# charger.net
KiCad netlist of a schematic drawn in EAGLE
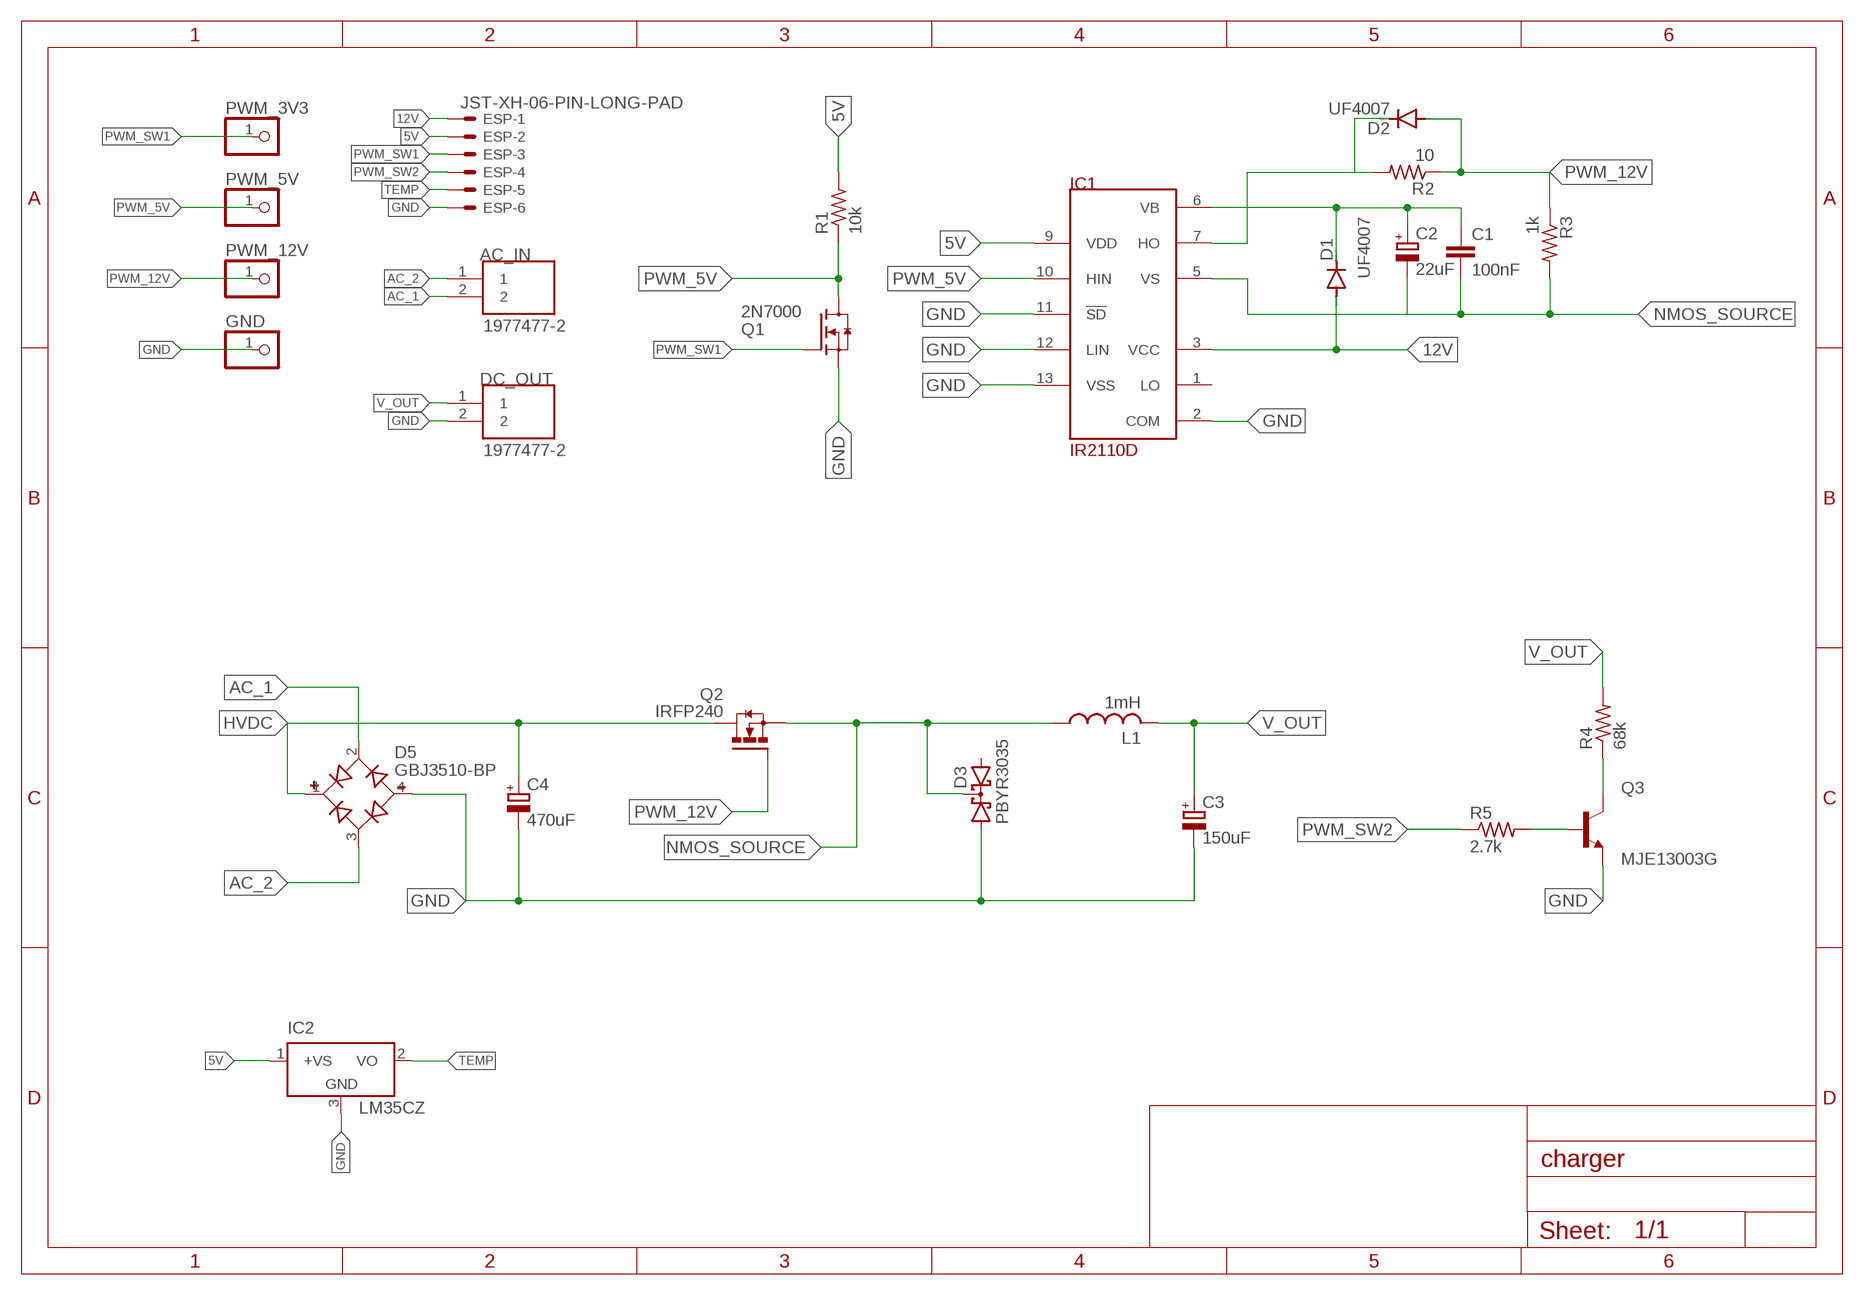
[diagram p0: schematic, sheet 1]

(export (version "E")
  (design (tool "Eeschema 10.0.6"))
  (components
    (comp (ref "AC_IN")
      (value "1977477-2")
      (footprint "eagle-import:TE_1977477-2")
      (fields (field (name "MF") "TE Connectivity"))
      (libsource (lib "eagle-import") (part "1977477-2"))
    )
    (comp (ref "C1")
      (value "100nF")
      (footprint "eagle-import:C025-025X050")
      (libsource (lib "eagle-import") (part "C-EU025-025X050"))
    )
    (comp (ref "C2")
      (value "22uF")
      (footprint "eagle-import:E2,5-6E")
      (libsource (lib "eagle-import") (part "CPOL-EUE2,5-6E"))
    )
    (comp (ref "C3")
      (value "150uF")
      (footprint "eagle-import:E7,5-18")
      (libsource (lib "eagle-import") (part "CPOL-EUE7.5-18"))
    )
    (comp (ref "C4")
      (value "470uF")
      (footprint "eagle-import:EB35D")
      (libsource (lib "eagle-import") (part "CPOL-EUE10-35"))
    )
    (comp (ref "D1")
      (value "UF4007")
      (footprint "eagle-import:DO34-7")
      (libsource (lib "eagle-import") (part "BAS15"))
    )
    (comp (ref "D2")
      (value "UF4007")
      (footprint "eagle-import:DO34-7")
      (libsource (lib "eagle-import") (part "BAS15"))
    )
    (comp (ref "D3")
      (value "PBYR3035")
      (footprint "eagle-import:SOT93S")
      (libsource (lib "eagle-import") (part "PBYR3035"))
    )
    (comp (ref "D5")
      (value "GBJ3510-BP")
      (footprint "eagle-import:DIOB_GBJ3510-BP")
      (fields (field (name "MF") "Micro Commercial"))
      (libsource (lib "eagle-import") (part "GBJ3510-BP"))
    )
    (comp (ref "DC_OUT")
      (value "1977477-2")
      (footprint "eagle-import:TE_1977477-2")
      (fields (field (name "MF") "TE Connectivity"))
      (libsource (lib "eagle-import") (part "1977477-2"))
    )
    (comp (ref "ESP")
      (value "JST-XH-06-PIN-LONG-PAD")
      (footprint "eagle-import:JST-XH-06-PACKAGE-LONG-PAD")
      (libsource (lib "eagle-import") (part "JST-XH-06-PIN-LONG-PAD"))
    )
    (comp (ref "GND")
      (value "PINHD-1X1")
      (footprint "eagle-import:1X01")
      (libsource (lib "eagle-import") (part "PINHD-1X1"))
    )
    (comp (ref "IC1")
      (value "IR2110D")
      (footprint "eagle-import:DIL14")
      (libsource (lib "eagle-import") (part "IR2110D"))
    )
    (comp (ref "IC2")
      (value "LM35CZ")
      (footprint "eagle-import:TO92")
      (libsource (lib "eagle-import") (part "LM35CZ"))
    )
    (comp (ref "L1")
      (value "1mH")
      (footprint "eagle-import:TJ7-U1")
      (libsource (lib "eagle-import") (part "L-USTJ7-U1"))
    )
    (comp (ref "PWM_3V3")
      (value "PINHD-1X1")
      (footprint "eagle-import:1X01")
      (libsource (lib "eagle-import") (part "PINHD-1X1"))
    )
    (comp (ref "PWM_5V")
      (value "PINHD-1X1")
      (footprint "eagle-import:1X01")
      (libsource (lib "eagle-import") (part "PINHD-1X1"))
    )
    (comp (ref "PWM_12V")
      (value "PINHD-1X1")
      (footprint "eagle-import:1X01")
      (libsource (lib "eagle-import") (part "PINHD-1X1"))
    )
    (comp (ref "Q1")
      (value "2N7000")
      (footprint "eagle-import:TO92")
      (fields (field (name "MF") "STMicroelectronics"))
      (libsource (lib "eagle-import") (part "2N7000"))
    )
    (comp (ref "Q2")
      (value "IRFP240")
      (footprint "eagle-import:TO247AC")
      (fields (field (name "MF") "Vishay Siliconix"))
      (libsource (lib "eagle-import") (part "IRFP240"))
    )
    (comp (ref "Q3")
      (value "MJE13003G")
      (footprint "eagle-import:TO229P780X300X1364-3")
      (fields (field (name "MF") "ON Semiconductor"))
      (libsource (lib "eagle-import") (part "MJE13003G"))
    )
    (comp (ref "R1")
      (value "10k")
      (footprint "eagle-import:0204_7")
      (libsource (lib "eagle-import") (part "R-US_0204/7"))
    )
    (comp (ref "R2")
      (value "10")
      (footprint "eagle-import:0204_7")
      (libsource (lib "eagle-import") (part "R-US_0204/7"))
    )
    (comp (ref "R3")
      (value "1k")
      (footprint "eagle-import:0204_7")
      (libsource (lib "eagle-import") (part "R-US_0204/7"))
    )
    (comp (ref "R4")
      (value "68k")
      (footprint "eagle-import:0204_7")
      (libsource (lib "eagle-import") (part "R-US_0204/7"))
    )
    (comp (ref "R5")
      (value "2.7k")
      (footprint "eagle-import:0204_7")
      (libsource (lib "eagle-import") (part "R-US_0204/7"))
    )
  )
  (nets
    (net (code "1") (name "5V") (class "Default")
      (node (ref "ESP") (pin "2") (pinfunction "S_2") (pintype "passive"))
      (node (ref "IC1") (pin "9") (pinfunction "VDD_9") (pintype "power_in"))
      (node (ref "IC2") (pin "1") (pinfunction "+VS_1") (pintype "input"))
      (node (ref "R1") (pin "2") (pinfunction "2_2") (pintype "passive"))
    )
    (net (code "2") (name "12V") (class "Default")
      (node (ref "D1") (pin "A") (pinfunction "A_A") (pintype "passive"))
      (node (ref "ESP") (pin "1") (pinfunction "S_1") (pintype "passive"))
      (node (ref "IC1") (pin "3") (pinfunction "VCC_3") (pintype "power_in"))
    )
    (net (code "3") (name "AC_1") (class "Default")
      (node (ref "AC_IN") (pin "2") (pinfunction "2_2") (pintype "passive"))
      (node (ref "D5") (pin "2") (pinfunction "AC1_2") (pintype "passive"))
    )
    (net (code "4") (name "AC_2") (class "Default")
      (node (ref "AC_IN") (pin "1") (pinfunction "1_1") (pintype "passive"))
      (node (ref "D5") (pin "3") (pinfunction "AC2_3") (pintype "passive"))
    )
    (net (code "5") (name "GND") (class "Default")
      (node (ref "C3") (pin "-") (pinfunction "-_-") (pintype "passive"))
      (node (ref "C4") (pin "-") (pinfunction "-_-") (pintype "passive"))
      (node (ref "D3") (pin "A1") (pinfunction "A1_A1") (pintype "passive"))
      (node (ref "D5") (pin "4") (pinfunction "-_4") (pintype "passive"))
      (node (ref "DC_OUT") (pin "2") (pinfunction "2_2") (pintype "passive"))
      (node (ref "ESP") (pin "6") (pinfunction "S_6") (pintype "passive"))
      (node (ref "GND") (pin "1") (pinfunction "1_1") (pintype "passive"))
      (node (ref "IC1") (pin "11") (pinfunction "~{SD}_11") (pintype "input"))
      (node (ref "IC1") (pin "12") (pinfunction "LIN_12") (pintype "input"))
      (node (ref "IC1") (pin "13") (pinfunction "VSS_13") (pintype "power_in"))
      (node (ref "IC1") (pin "2") (pinfunction "COM_2") (pintype "power_in"))
      (node (ref "IC2") (pin "3") (pinfunction "GND_3") (pintype "power_in"))
      (node (ref "Q1") (pin "1") (pinfunction "S_1") (pintype "passive"))
      (node (ref "Q3") (pin "3") (pinfunction "E_3") (pintype "passive"))
    )
    (net (code "6") (name "HVDC") (class "Default")
      (node (ref "C4") (pin "+") (pinfunction "+_+") (pintype "passive"))
      (node (ref "D5") (pin "1") (pinfunction "+_1") (pintype "passive"))
      (node (ref "Q2") (pin "2") (pinfunction "D_2") (pintype "passive"))
    )
    (net (code "7") (name "NMOS_SOURCE") (class "Default")
      (node (ref "C1") (pin "2") (pinfunction "2_2") (pintype "passive"))
      (node (ref "C2") (pin "-") (pinfunction "-_-") (pintype "passive"))
      (node (ref "D3") (pin "C") (pinfunction "C_C") (pintype "passive"))
      (node (ref "IC1") (pin "5") (pinfunction "VS_5") (pintype "power_in"))
      (node (ref "L1") (pin "1") (pinfunction "1_1") (pintype "passive"))
      (node (ref "Q2") (pin "3") (pinfunction "S_3") (pintype "passive"))
      (node (ref "R3") (pin "2") (pinfunction "2_2") (pintype "passive"))
    )
    (net (code "8") (name "Net-(IC1-HO)") (class "Default")
      (node (ref "D2") (pin "C") (pinfunction "C_C") (pintype "passive"))
      (node (ref "IC1") (pin "7") (pinfunction "HO_7") (pintype "output"))
      (node (ref "R2") (pin "2") (pinfunction "2_2") (pintype "passive"))
    )
    (net (code "9") (name "Net-(IC1-VB)") (class "Default")
      (node (ref "C1") (pin "1") (pinfunction "1_1") (pintype "passive"))
      (node (ref "C2") (pin "+") (pinfunction "+_+") (pintype "passive"))
      (node (ref "D1") (pin "C") (pinfunction "C_C") (pintype "passive"))
      (node (ref "IC1") (pin "6") (pinfunction "VB_6") (pintype "power_in"))
    )
    (net (code "10") (name "Net-(Q3-B)") (class "Default")
      (node (ref "Q3") (pin "1") (pinfunction "B_1") (pintype "passive"))
      (node (ref "R5") (pin "2") (pinfunction "2_2") (pintype "passive"))
    )
    (net (code "11") (name "Net-(Q3-C)") (class "Default")
      (node (ref "Q3") (pin "2") (pinfunction "C_2") (pintype "passive"))
      (node (ref "R4") (pin "1") (pinfunction "1_1") (pintype "passive"))
    )
    (net (code "12") (name "PWM_5V") (class "Default")
      (node (ref "IC1") (pin "10") (pinfunction "HIN_10") (pintype "input"))
      (node (ref "PWM_5V") (pin "1") (pinfunction "1_1") (pintype "passive"))
      (node (ref "Q1") (pin "3") (pinfunction "D_3") (pintype "passive"))
      (node (ref "R1") (pin "1") (pinfunction "1_1") (pintype "passive"))
    )
    (net (code "13") (name "PWM_12V") (class "Default")
      (node (ref "D2") (pin "A") (pinfunction "A_A") (pintype "passive"))
      (node (ref "PWM_12V") (pin "1") (pinfunction "1_1") (pintype "passive"))
      (node (ref "Q2") (pin "1") (pinfunction "G_1") (pintype "passive"))
      (node (ref "R2") (pin "1") (pinfunction "1_1") (pintype "passive"))
      (node (ref "R3") (pin "1") (pinfunction "1_1") (pintype "passive"))
    )
    (net (code "14") (name "PWM_SW1") (class "Default")
      (node (ref "ESP") (pin "3") (pinfunction "S_3") (pintype "passive"))
      (node (ref "PWM_3V3") (pin "1") (pinfunction "1_1") (pintype "passive"))
      (node (ref "Q1") (pin "2") (pinfunction "G_2") (pintype "passive"))
    )
    (net (code "15") (name "PWM_SW2") (class "Default")
      (node (ref "ESP") (pin "4") (pinfunction "S_4") (pintype "passive"))
      (node (ref "R5") (pin "1") (pinfunction "1_1") (pintype "passive"))
    )
    (net (code "16") (name "TEMP") (class "Default")
      (node (ref "ESP") (pin "5") (pinfunction "S_5") (pintype "passive"))
      (node (ref "IC2") (pin "2") (pinfunction "VO_2") (pintype "input"))
    )
    (net (code "17") (name "V_OUT") (class "Default")
      (node (ref "C3") (pin "+") (pinfunction "+_+") (pintype "passive"))
      (node (ref "DC_OUT") (pin "1") (pinfunction "1_1") (pintype "passive"))
      (node (ref "L1") (pin "2") (pinfunction "2_2") (pintype "passive"))
      (node (ref "R4") (pin "2") (pinfunction "2_2") (pintype "passive"))
    )
    (net (code "18") (name "unconnected-(D3-PadA2)") (class "Default")
      (node (ref "D3") (pin "A2") (pinfunction "A2_A2") (pintype "passive"))
    )
    (net (code "19") (name "unconnected-(IC1-LO-Pad1)") (class "Default")
      (node (ref "IC1") (pin "1") (pinfunction "LO_1") (pintype "output"))
    )
  )
)
